# SCH_555-Circuit_2025-03-19.net
KiCad netlist of a schematic drawn in EasyEDA
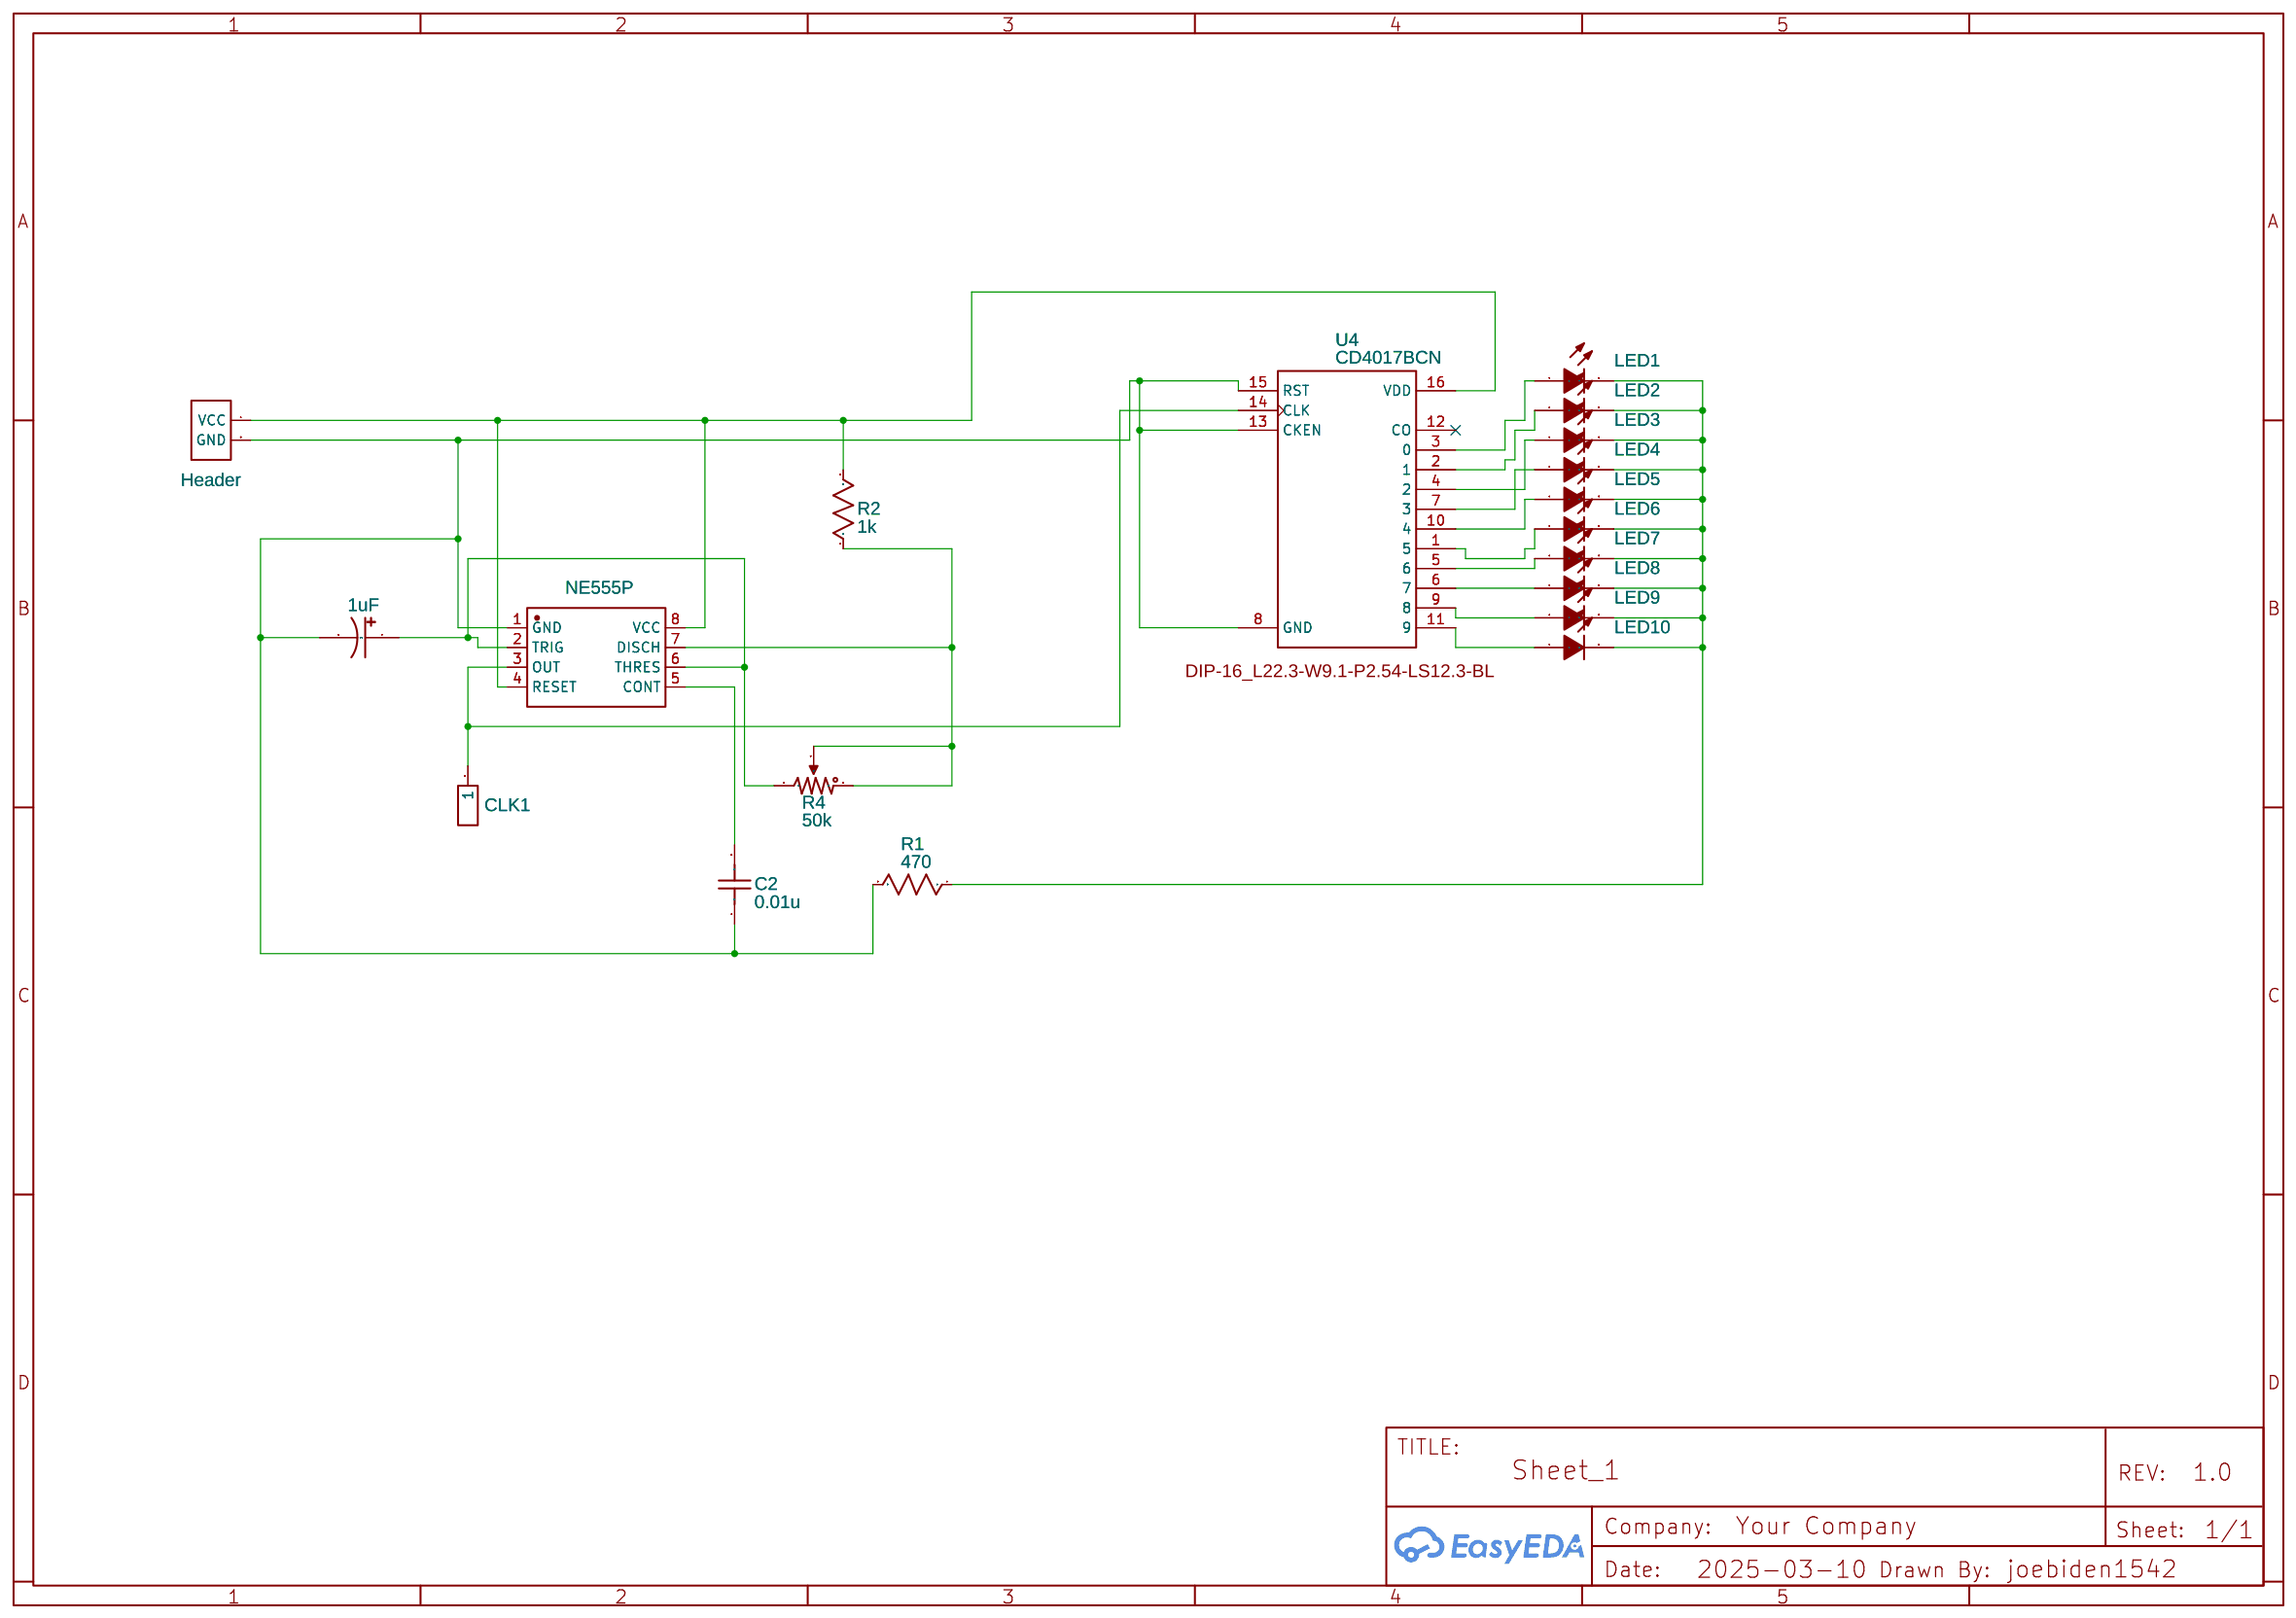
[diagram p0: schematic sheet]

(export (version "E")
  (design (tool "Eeschema 10.0.6"))
  (components
    (comp (ref "C1")
      (value "1uF")
      (fields (field (name "Manufacturer Part") "UVZ1H010MDD") (field (name "Manufacturer") "Nichicon(尼吉康)"))
      (libsource (lib "") (part "UVZ1H010MDD"))
    )
    (comp (ref "C2") (value "0.01u") (libsource (lib "") (part "C_0603_US")))
    (comp (ref "CLK1")
      (value "C81276")
      (fields
        (field (name "Manufacturer Part") "2.54-1*1P针")
        (field (name "Manufacturer") "BOOMELE(Boom Precision Elec)")
      )
      (libsource (lib "") (part "Header-Male-2.54_1x1"))
    )
    (comp (ref "H1") (value "Header") (libsource (lib "") (part "HEADER-FEMALE-2.54_1X2")))
    (comp (ref "LED1") (value "LED_5MM") (libsource (lib "") (part "LED_5MM")))
    (comp (ref "LED2") (value "LED_5MM") (libsource (lib "") (part "LED_5MM")))
    (comp (ref "LED3") (value "LED_5MM") (libsource (lib "") (part "LED_5MM")))
    (comp (ref "LED4") (value "LED_5MM") (libsource (lib "") (part "LED_5MM")))
    (comp (ref "LED5") (value "LED_5MM") (libsource (lib "") (part "LED_5MM")))
    (comp (ref "LED6") (value "LED_5MM") (libsource (lib "") (part "LED_5MM")))
    (comp (ref "LED7") (value "LED_5MM") (libsource (lib "") (part "LED_5MM")))
    (comp (ref "LED8") (value "LED_5MM") (libsource (lib "") (part "LED_5MM")))
    (comp (ref "LED9") (value "LED_5MM") (libsource (lib "") (part "LED_5MM")))
    (comp (ref "LED10") (value "LED_5MM") (libsource (lib "") (part "LED_5MM")))
    (comp (ref "R1")
      (value "470")
      (fields (field (name "Manufacturer Part") "?"))
      (libsource (lib "") (part "Resistor"))
    )
    (comp (ref "R2")
      (value "1k")
      (fields (field (name "Manufacturer Part") "?"))
      (libsource (lib "") (part "Resistor_1"))
    )
    (comp (ref "R4")
      (value "50k")
      (fields (field (name "Manufacturer Part") "?"))
      (libsource (lib "") (part "Potentiometer"))
    )
    (comp (ref "U2")
      (value "NE555P")
      (fields (field (name "Manufacturer") "TI(德州仪器)"))
      (libsource (lib "") (part "NE555P"))
    )
    (comp (ref "U4") (value "CD4017BCN") (libsource (lib "") (part "CD4017BCN")))
  )
  (nets
    (net (code "1") (name "Net-(H1-GND)") (class "Default")
      (node (ref "C1") (pin "2") (pinfunction "2_2") (pintype "unspecified"))
      (node (ref "C2") (pin "1") (pinfunction "1_1") (pintype "unspecified"))
      (node (ref "H1") (pin "2") (pinfunction "GND_2") (pintype "unspecified"))
      (node (ref "R1") (pin "2") (pinfunction "2_2") (pintype "unspecified"))
      (node (ref "U2") (pin "1") (pinfunction "GND_1") (pintype "unspecified"))
      (node (ref "U4") (pin "13") (pinfunction "CKEN_13") (pintype "unspecified"))
      (node (ref "U4") (pin "15") (pinfunction "RST_15") (pintype "unspecified"))
      (node (ref "U4") (pin "8") (pinfunction "GND_8") (pintype "passive"))
    )
    (net (code "2") (name "Net-(H1-VCC)") (class "Default")
      (node (ref "H1") (pin "1") (pinfunction "VCC_1") (pintype "unspecified"))
      (node (ref "R2") (pin "2") (pinfunction "2_2") (pintype "unspecified"))
      (node (ref "U2") (pin "4") (pinfunction "RESET_4") (pintype "unspecified"))
      (node (ref "U2") (pin "8") (pinfunction "VCC_8") (pintype "unspecified"))
      (node (ref "U4") (pin "16") (pinfunction "VDD_16") (pintype "passive"))
    )
    (net (code "3") (name "Net-(LED1-A)") (class "Default")
      (node (ref "LED1") (pin "1") (pinfunction "A_1") (pintype "input"))
      (node (ref "U4") (pin "3") (pinfunction "0_3") (pintype "output"))
    )
    (net (code "4") (name "Net-(LED1-K)") (class "Default")
      (node (ref "LED1") (pin "2") (pinfunction "K_2") (pintype "input"))
      (node (ref "LED10") (pin "2") (pinfunction "K_2") (pintype "input"))
      (node (ref "LED2") (pin "2") (pinfunction "K_2") (pintype "input"))
      (node (ref "LED3") (pin "2") (pinfunction "K_2") (pintype "input"))
      (node (ref "LED4") (pin "2") (pinfunction "K_2") (pintype "input"))
      (node (ref "LED5") (pin "2") (pinfunction "K_2") (pintype "input"))
      (node (ref "LED6") (pin "2") (pinfunction "K_2") (pintype "input"))
      (node (ref "LED7") (pin "2") (pinfunction "K_2") (pintype "input"))
      (node (ref "LED8") (pin "2") (pinfunction "K_2") (pintype "input"))
      (node (ref "LED9") (pin "2") (pinfunction "K_2") (pintype "input"))
      (node (ref "R1") (pin "1") (pinfunction "1_1") (pintype "unspecified"))
    )
    (net (code "5") (name "Net-(LED2-A)") (class "Default")
      (node (ref "LED2") (pin "1") (pinfunction "A_1") (pintype "input"))
      (node (ref "U4") (pin "2") (pinfunction "1_2") (pintype "output"))
    )
    (net (code "6") (name "Net-(LED3-A)") (class "Default")
      (node (ref "LED3") (pin "1") (pinfunction "A_1") (pintype "input"))
      (node (ref "U4") (pin "4") (pinfunction "2_4") (pintype "output"))
    )
    (net (code "7") (name "Net-(LED4-A)") (class "Default")
      (node (ref "LED4") (pin "1") (pinfunction "A_1") (pintype "input"))
      (node (ref "U4") (pin "7") (pinfunction "3_7") (pintype "output"))
    )
    (net (code "8") (name "Net-(LED5-A)") (class "Default")
      (node (ref "LED5") (pin "1") (pinfunction "A_1") (pintype "input"))
      (node (ref "U4") (pin "10") (pinfunction "4_10") (pintype "output"))
    )
    (net (code "9") (name "Net-(LED6-A)") (class "Default")
      (node (ref "LED6") (pin "1") (pinfunction "A_1") (pintype "input"))
      (node (ref "U4") (pin "1") (pinfunction "5_1") (pintype "output"))
    )
    (net (code "10") (name "Net-(LED7-A)") (class "Default")
      (node (ref "LED7") (pin "1") (pinfunction "A_1") (pintype "input"))
      (node (ref "U4") (pin "5") (pinfunction "6_5") (pintype "output"))
    )
    (net (code "11") (name "Net-(LED8-A)") (class "Default")
      (node (ref "LED8") (pin "1") (pinfunction "A_1") (pintype "input"))
      (node (ref "U4") (pin "6") (pinfunction "7_6") (pintype "output"))
    )
    (net (code "12") (name "Net-(LED9-A)") (class "Default")
      (node (ref "LED9") (pin "1") (pinfunction "A_1") (pintype "input"))
      (node (ref "U4") (pin "9") (pinfunction "8_9") (pintype "output"))
    )
    (net (code "13") (name "Net-(LED10-A)") (class "Default")
      (node (ref "LED10") (pin "1") (pinfunction "A_1") (pintype "input"))
      (node (ref "U4") (pin "11") (pinfunction "9_11") (pintype "output"))
    )
    (net (code "14") (name "Net-(R4-2)") (class "Default")
      (node (ref "R2") (pin "1") (pinfunction "1_1") (pintype "unspecified"))
      (node (ref "R4") (pin "2") (pinfunction "3_2") (pintype "unspecified"))
      (node (ref "R4") (pin "3") (pinfunction "2_3") (pintype "unspecified"))
      (node (ref "U2") (pin "7") (pinfunction "DISCH_7") (pintype "unspecified"))
    )
    (net (code "15") (name "Net-(U2-CONT)") (class "Default")
      (node (ref "C2") (pin "2") (pinfunction "2_2") (pintype "unspecified"))
      (node (ref "U2") (pin "5") (pinfunction "CONT_5") (pintype "unspecified"))
    )
    (net (code "16") (name "Net-(U2-OUT)") (class "Default")
      (node (ref "CLK1") (pin "1") (pinfunction "1_1") (pintype "unspecified"))
      (node (ref "U2") (pin "3") (pinfunction "OUT_3") (pintype "unspecified"))
      (node (ref "U4") (pin "14") (pinfunction "CLK_14") (pintype "unspecified"))
    )
    (net (code "17") (name "Net-(U2-THRES)") (class "Default")
      (node (ref "C1") (pin "1") (pinfunction "1_1") (pintype "unspecified"))
      (node (ref "R4") (pin "1") (pinfunction "1_1") (pintype "unspecified"))
      (node (ref "U2") (pin "2") (pinfunction "TRIG_2") (pintype "unspecified"))
      (node (ref "U2") (pin "6") (pinfunction "THRES_6") (pintype "unspecified"))
    )
    (net (code "18") (name "unconnected-(U4-CO-Pad12)") (class "Default")
      (node (ref "U4") (pin "12") (pinfunction "CO_12") (pintype "output+no_connect"))
    )
  )
)
